# MainSwitch.net
KiCad netlist of a schematic drawn in Altium Designer
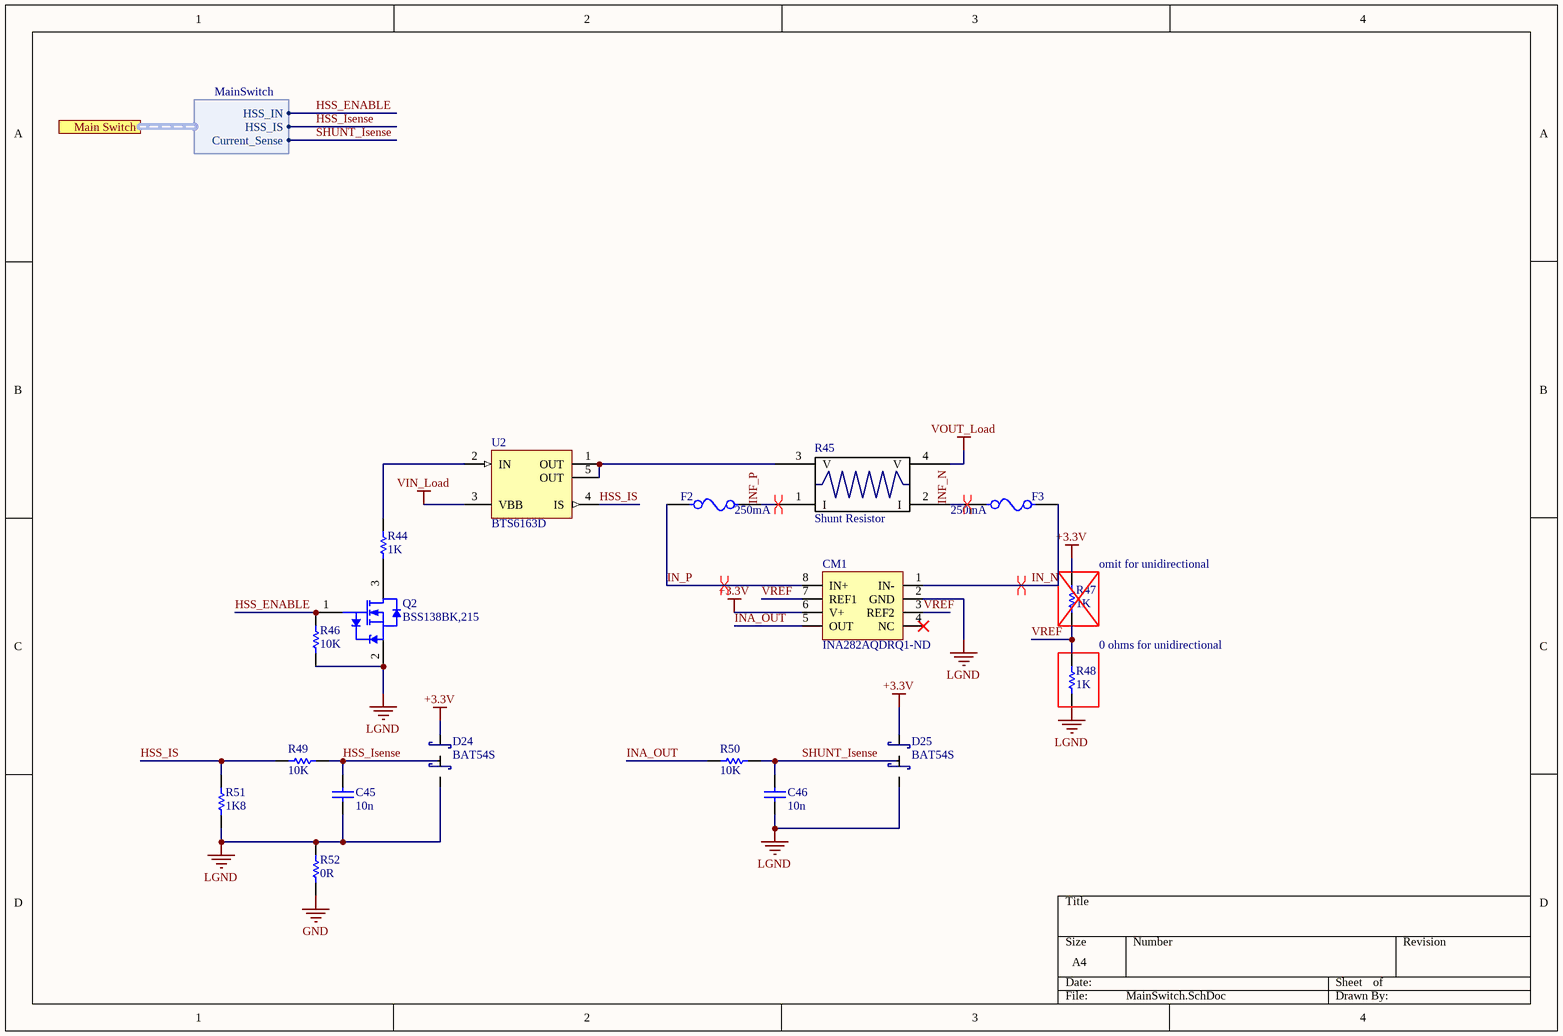
[diagram p0: MainSwitch.SchDoc]

(export (version "E")
  (design (tool "Eeschema 10.0.6"))
  (components
    (comp (ref "C45")
      (value "10n")
      (footprint "CAPC0603(1608)55_N")
      (description "Keramikvielschichtkondensator, SMD, Baureihe MC, ± 10%")
      (fields (field (name "MANUFACTURER") "TDK") (field (name "TOLERANCE") "± 10%"))
      (libsource (lib "Res&Caps") (part "Cap 10n"))
    )
    (comp (ref "C46")
      (value "10n")
      (footprint "CAPC0603(1608)55_N")
      (description "Keramikvielschichtkondensator, SMD, Baureihe MC, ± 10%")
      (fields (field (name "MANUFACTURER") "TDK") (field (name "TOLERANCE") "± 10%"))
      (libsource (lib "Res&Caps") (part "Cap 10n"))
    )
    (comp (ref "CM1")
      (value "INA282AQDRQ1")
      (footprint "SO8_N")
      (description "SP Amp Current Shunt Monitor Single 18V Automotive 8-Pin SOIC T/R")
      (fields
        (field (name "MANUFACTURER") "Texas Instruments")
        (field (name "SUPPLIER PART NUMBER 1") "INA282AQDRQ1-ND")
      )
      (libsource (lib "LV-BMS") (part "INA282AQDRQ1"))
    )
    (comp (ref "D24") (value "BAT54S") (footprint "_SOT23-3N") (libsource (lib "LV-BMS") (part "BAT54S")))
    (comp (ref "D25") (value "BAT54S") (footprint "_SOT23-3N") (libsource (lib "LV-BMS") (part "BAT54S")))
    (comp (ref "F2")
      (value "250mA")
      (footprint "RESC0603(1608)_N")
      (description "Fuse, Fast Blow 250mA, 63VDC")
      (fields (field (name "MANUFACTURER") "Bel Fuse"))
      (libsource (lib "LV-BMS") (part "Bel Fuse C2Q250"))
    )
    (comp (ref "F3")
      (value "250mA")
      (footprint "RESC0603(1608)_N")
      (description "Fuse, Fast Blow 250mA, 63VDC")
      (fields (field (name "MANUFACTURER") "Bel Fuse"))
      (libsource (lib "LV-BMS") (part "Bel Fuse C2Q250"))
    )
    (comp (ref "Q2")
      (value "BSS138BK,215")
      (footprint "NXP-SOT23_L")
      (description "N-Channel Trench MOSFET, 60 V, 0.36 A, -55 to 150 degC, 3-Pin SOT23, Tape and Reel")
      (fields (field (name "MANUFACTURER") "NXP Semiconductors"))
      (libsource (lib "Altium Content Vault") (part "NXP-NMOS-GSD-3"))
    )
    (comp (ref "R44")
      (value "1K")
      (footprint "RESC0603(1608)_N")
      (description "Chipwiderstand, SMD, Baureihe MC, 1%")
      (fields (field (name "MANUFACTURER") "Multicomp") (field (name "POWER") "100mW"))
      (libsource (lib "Res&Caps") (part "Res 1K"))
    )
    (comp (ref "R45")
      (value "Shunt Resistor")
      (footprint "SHUNT FC4L110")
      (fields (field (name "MANUFACTURER") "OHMITE") (field (name "PUBLISHER") "Altium Limited"))
      (libsource (lib "LV-BMS") (part "Shunt 0R003"))
    )
    (comp (ref "R46")
      (value "10K")
      (footprint "RESC0603(1608)_N")
      (description "Chipwiderstand, SMD, Baureihe MC, 1%")
      (fields (field (name "MANUFACTURER") "Multicomp") (field (name "POWER") "100mW"))
      (libsource (lib "Res&Caps") (part "Res 10K"))
    )
    (comp (ref "R47")
      (value "1K")
      (footprint "RESC0603(1608)_N")
      (description "Chipwiderstand, SMD, Baureihe MC, 1%")
      (fields (field (name "MANUFACTURER") "Multicomp") (field (name "POWER") "100mW"))
      (libsource (lib "Res&Caps") (part "Res 1K"))
    )
    (comp (ref "R48")
      (value "1K")
      (footprint "RESC0603(1608)_N")
      (description "Chipwiderstand, SMD, Baureihe MC, 1%")
      (fields (field (name "MANUFACTURER") "Multicomp") (field (name "POWER") "100mW"))
      (libsource (lib "Res&Caps") (part "Res 1K"))
    )
    (comp (ref "R49")
      (value "10K")
      (footprint "RESC0603(1608)_N")
      (description "Chipwiderstand, SMD, Baureihe MC, 1%")
      (fields (field (name "MANUFACTURER") "Multicomp") (field (name "POWER") "100mW"))
      (libsource (lib "Res&Caps") (part "Res 10K"))
    )
    (comp (ref "R50")
      (value "10K")
      (footprint "RESC0603(1608)_N")
      (description "Chipwiderstand, SMD, Baureihe MC, 1%")
      (fields (field (name "MANUFACTURER") "Multicomp") (field (name "POWER") "100mW"))
      (libsource (lib "Res&Caps") (part "Res 10K"))
    )
    (comp (ref "R51")
      (value "1K8")
      (footprint "RESC0603(1608)_N")
      (description "Chipwiderstand, SMD, Baureihe MC, 1%")
      (fields (field (name "MANUFACTURER") "Multicomp") (field (name "POWER") "100mW"))
      (libsource (lib "Res&Caps") (part "Res 1K8"))
    )
    (comp (ref "R52")
      (value "0R")
      (footprint "RESC0603(1608)_N")
      (description "Chipwiderstand, SMD, Baureihe MC, 1%")
      (fields (field (name "MANUFACTURER") "Multicomp") (field (name "POWER") "100mW"))
      (libsource (lib "Res&Caps") (part "Res 0R"))
    )
    (comp (ref "U2")
      (value "BTS6163D")
      (footprint "INF-PG-TO252-5-11_L")
      (fields (field (name "MANUFACTURER") "Infineon"))
      (libsource (lib "LV-BMS") (part "BTS6163D"))
    )
  )
  (nets
    (net (code "2") (name "+3.3V") (class "Default")
      (node (ref "CM1") (pin "6") (pinfunction "V+_6") (pintype "passive"))
      (node (ref "D24") (pin "2") (pinfunction "2_2") (pintype "passive"))
      (node (ref "D25") (pin "2") (pinfunction "2_2") (pintype "passive"))
      (node (ref "R47") (pin "2") (pinfunction "2_2") (pintype "passive"))
    )
    (net (code "3") (name "/HSS_ENABLE") (class "Default")
      (node (ref "Q2") (pin "1") (pinfunction "G_1") (pintype "passive"))
      (node (ref "R46") (pin "2") (pinfunction "2_2") (pintype "passive"))
    )
    (net (code "4") (name "/HSS_IS") (class "Default")
      (node (ref "R49") (pin "1") (pinfunction "1_1") (pintype "passive"))
      (node (ref "R51") (pin "2") (pinfunction "2_2") (pintype "passive"))
      (node (ref "U2") (pin "4") (pinfunction "IS_4") (pintype "output"))
    )
    (net (code "5") (name "/HSS_Isense") (class "Default")
      (node (ref "C45") (pin "2") (pinfunction "2_2") (pintype "passive"))
      (node (ref "D24") (pin "3") (pinfunction "3_3") (pintype "passive"))
      (node (ref "R49") (pin "2") (pinfunction "2_2") (pintype "passive"))
    )
    (net (code "6") (name "/INA_OUT") (class "Default")
      (node (ref "CM1") (pin "5") (pinfunction "OUT_5") (pintype "passive"))
      (node (ref "R50") (pin "1") (pinfunction "1_1") (pintype "passive"))
    )
    (net (code "7") (name "/INF_N") (class "Default")
      (node (ref "F3") (pin "2") (pinfunction "2_2") (pintype "passive"))
      (node (ref "R45") (pin "2") (pinfunction "I_2") (pintype "passive"))
    )
    (net (code "8") (name "/INF_P") (class "Default")
      (node (ref "F2") (pin "1") (pinfunction "1_1") (pintype "passive"))
      (node (ref "R45") (pin "1") (pinfunction "I_1") (pintype "passive"))
    )
    (net (code "9") (name "/IN_N") (class "Default")
      (node (ref "CM1") (pin "1") (pinfunction "IN-_1") (pintype "passive"))
      (node (ref "F3") (pin "1") (pinfunction "1_1") (pintype "passive"))
    )
    (net (code "10") (name "/IN_P") (class "Default")
      (node (ref "CM1") (pin "8") (pinfunction "IN+_8") (pintype "passive"))
      (node (ref "F2") (pin "2") (pinfunction "2_2") (pintype "passive"))
    )
    (net (code "11") (name "/SHUNT_Isense") (class "Default")
      (node (ref "C46") (pin "2") (pinfunction "2_2") (pintype "passive"))
      (node (ref "D25") (pin "3") (pinfunction "3_3") (pintype "passive"))
      (node (ref "R50") (pin "2") (pinfunction "2_2") (pintype "passive"))
    )
    (net (code "12") (name "/VREF") (class "Default")
      (node (ref "CM1") (pin "3") (pinfunction "REF2_3") (pintype "passive"))
      (node (ref "CM1") (pin "7") (pinfunction "REF1_7") (pintype "passive"))
      (node (ref "R47") (pin "1") (pinfunction "1_1") (pintype "passive"))
      (node (ref "R48") (pin "2") (pinfunction "2_2") (pintype "passive"))
    )
    (net (code "14") (name "GND") (class "Default")
      (node (ref "R52") (pin "1") (pinfunction "1_1") (pintype "passive"))
    )
    (net (code "15") (name "LGND") (class "Default")
      (node (ref "C45") (pin "1") (pinfunction "1_1") (pintype "passive"))
      (node (ref "C46") (pin "1") (pinfunction "1_1") (pintype "passive"))
      (node (ref "CM1") (pin "2") (pinfunction "GND_2") (pintype "passive"))
      (node (ref "D24") (pin "1") (pinfunction "1_1") (pintype "passive"))
      (node (ref "D25") (pin "1") (pinfunction "1_1") (pintype "passive"))
      (node (ref "Q2") (pin "2") (pinfunction "S_2") (pintype "passive"))
      (node (ref "R46") (pin "1") (pinfunction "1_1") (pintype "passive"))
      (node (ref "R48") (pin "1") (pinfunction "1_1") (pintype "passive"))
      (node (ref "R51") (pin "1") (pinfunction "1_1") (pintype "passive"))
      (node (ref "R52") (pin "2") (pinfunction "2_2") (pintype "passive"))
    )
    (net (code "16") (name "Net-(Q2-D)") (class "Default")
      (node (ref "Q2") (pin "3") (pinfunction "D_3") (pintype "passive"))
      (node (ref "R44") (pin "1") (pinfunction "1_1") (pintype "passive"))
    )
    (net (code "17") (name "Net-(R45-V-Pad3)") (class "Default")
      (node (ref "R45") (pin "3") (pinfunction "V_3") (pintype "passive"))
      (node (ref "U2") (pin "1") (pinfunction "OUT_1") (pintype "tri_state"))
      (node (ref "U2") (pin "5") (pinfunction "OUT_5") (pintype "tri_state"))
    )
    (net (code "18") (name "Net-(U2-IN)") (class "Default")
      (node (ref "R44") (pin "2") (pinfunction "2_2") (pintype "passive"))
      (node (ref "U2") (pin "2") (pinfunction "IN_2") (pintype "input"))
    )
    (net (code "19") (name "VIN_Load") (class "Default")
      (node (ref "U2") (pin "3") (pinfunction "VBB_3") (pintype "power_in"))
    )
    (net (code "20") (name "VOUT_Load") (class "Default")
      (node (ref "R45") (pin "4") (pinfunction "V_4") (pintype "passive"))
    )
    (net (code "21") (name "unconnected-(CM1-NC-Pad4)") (class "Default")
      (node (ref "CM1") (pin "4") (pinfunction "NC_4") (pintype "passive+no_connect"))
    )
  )
)
